# mqttSwitch2_0.net
KiCad netlist of a schematic drawn in EAGLE
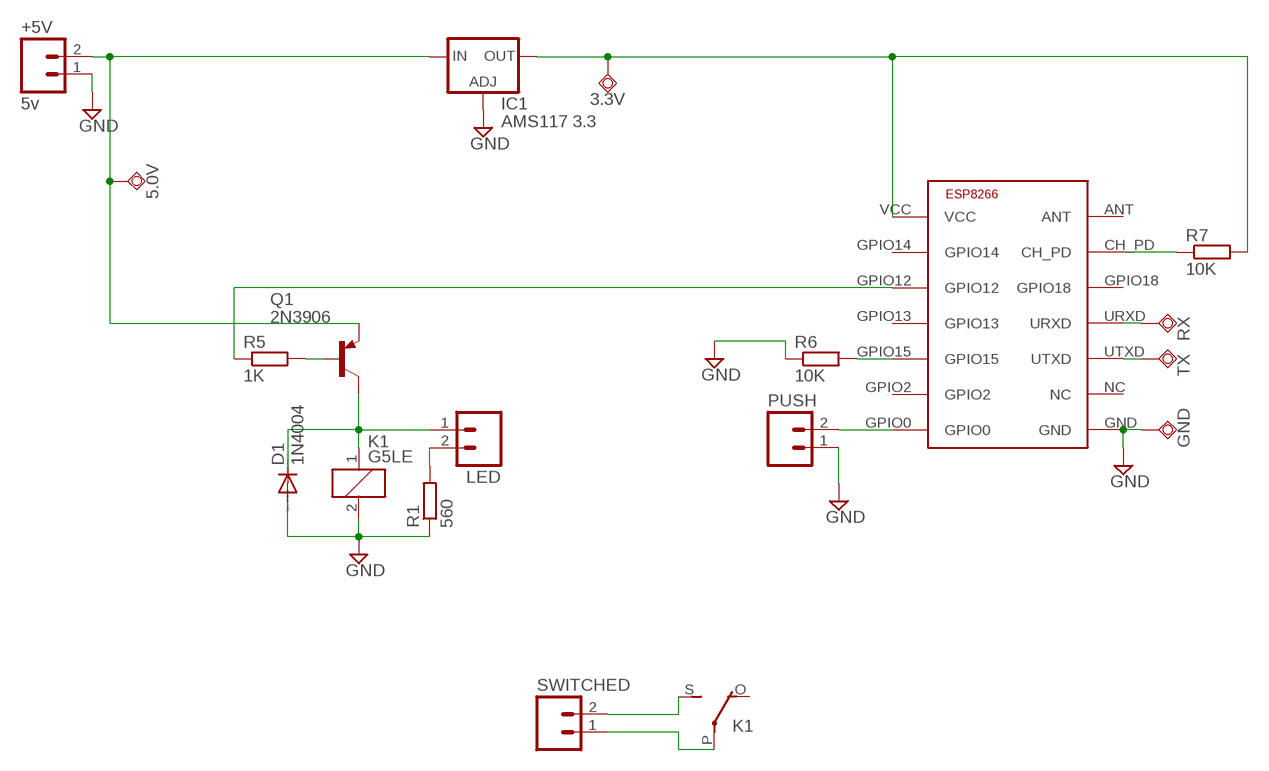
[diagram p0: schematic, sheet 1]

(export (version "E")
  (design (tool "Eeschema 10.0.6"))
  (components
    (comp (ref "+5V")
      (value "5v")
      (footprint "eagle-import:1X02")
      (libsource (lib "eagle-import") (part "M02PTH"))
    )
    (comp (ref "3.3V")
      (value "TPSQTP19R")
      (footprint "eagle-import:TP19R")
      (libsource (lib "eagle-import") (part "TPSQTP19R"))
    )
    (comp (ref "5.0V")
      (value "TPSQTP19R")
      (footprint "eagle-import:TP19R")
      (libsource (lib "eagle-import") (part "TPSQTP19R"))
    )
    (comp (ref "D1")
      (value "1N4004")
      (footprint "eagle-import:DO41-10")
      (libsource (lib "eagle-import") (part "1N4004"))
    )
    (comp (ref "GND")
      (value "TPSQTP19R")
      (footprint "eagle-import:TP19R")
      (libsource (lib "eagle-import") (part "TPSQTP19R"))
    )
    (comp (ref "IC1")
      (value "AMS117 3.3")
      (footprint "eagle-import:SOT223")
      (libsource (lib "eagle-import") (part "LD117A?S33TR"))
    )
    (comp (ref "K1")
      (value "G5LE")
      (footprint "eagle-import:G5LE")
      (libsource (lib "eagle-import") (part "G5LE"))
    )
    (comp (ref "LED")
      (value "M02PTH")
      (footprint "eagle-import:1X02")
      (libsource (lib "eagle-import") (part "M02PTH"))
    )
    (comp (ref "PUSH")
      (value "M02PTH")
      (footprint "eagle-import:1X02")
      (libsource (lib "eagle-import") (part "M02PTH"))
    )
    (comp (ref "Q1")
      (value "2N3906")
      (footprint "eagle-import:TO92")
      (libsource (lib "eagle-import") (part "2N3906"))
    )
    (comp (ref "R1")
      (value "560")
      (footprint "eagle-import:R0805")
      (libsource (lib "eagle-import") (part "R-EU_R0805"))
    )
    (comp (ref "R5")
      (value "1K")
      (footprint "eagle-import:R0805")
      (libsource (lib "eagle-import") (part "R-EU_R0805"))
    )
    (comp (ref "R6")
      (value "10K")
      (footprint "eagle-import:R0805")
      (libsource (lib "eagle-import") (part "R-EU_R0805"))
    )
    (comp (ref "R7")
      (value "10K")
      (footprint "eagle-import:R0805")
      (libsource (lib "eagle-import") (part "R-EU_R0805"))
    )
    (comp (ref "RX")
      (value "TPSQTP19R")
      (footprint "eagle-import:TP19R")
      (libsource (lib "eagle-import") (part "TPSQTP19R"))
    )
    (comp (ref "SWITCHED")
      (value "M02PTH4")
      (footprint "eagle-import:1X02_XTRA_BIG")
      (libsource (lib "eagle-import") (part "M02PTH4"))
    )
    (comp (ref "TX")
      (value "TPSQTP19R")
      (footprint "eagle-import:TP19R")
      (libsource (lib "eagle-import") (part "TPSQTP19R"))
    )
    (comp (ref "U$1")
      (value "ESP8266")
      (footprint "eagle-import:ESP-03")
      (libsource (lib "eagle-import") (part "ESP8266"))
    )
  )
  (nets
    (net (code "1") (name "GND") (class "Default")
      (node (ref "+5V") (pin "1") (pinfunction "1_1") (pintype "passive"))
      (node (ref "D1") (pin "A") (pinfunction "A_A") (pintype "passive"))
      (node (ref "GND") (pin "TP") (pinfunction "TP_TP") (pintype "input"))
      (node (ref "IC1") (pin "1") (pinfunction "ADJ_1") (pintype "input"))
      (node (ref "K1") (pin "2") (pinfunction "2_2") (pintype "passive"))
      (node (ref "PUSH") (pin "1") (pinfunction "1_1") (pintype "passive"))
      (node (ref "R1") (pin "1") (pinfunction "1_1") (pintype "passive"))
      (node (ref "R6") (pin "1") (pinfunction "1_1") (pintype "passive"))
      (node (ref "U$1") (pin "GND") (pinfunction "GND_GND") (pintype "bidirectional"))
    )
    (net (code "2") (name "Net-(IC1-IN)") (class "Default")
      (node (ref "+5V") (pin "2") (pinfunction "2_2") (pintype "passive"))
      (node (ref "5.0V") (pin "TP") (pinfunction "TP_TP") (pintype "input"))
      (node (ref "IC1") (pin "3") (pinfunction "IN_3") (pintype "input"))
      (node (ref "Q1") (pin "3") (pinfunction "E_3") (pintype "passive"))
    )
    (net (code "3") (name "Net-(IC1-OUT)") (class "Default")
      (node (ref "3.3V") (pin "TP") (pinfunction "TP_TP") (pintype "input"))
      (node (ref "IC1") (pin "4") (pinfunction "OUT_4") (pintype "passive"))
      (node (ref "R7") (pin "2") (pinfunction "2_2") (pintype "passive"))
      (node (ref "U$1") (pin "VCC") (pinfunction "VCC_VCC") (pintype "bidirectional"))
    )
    (net (code "4") (name "Net-(K1-PadP)") (class "Default")
      (node (ref "K1") (pin "P") (pinfunction "P_P") (pintype "passive"))
      (node (ref "SWITCHED") (pin "1") (pinfunction "1_1") (pintype "passive"))
    )
    (net (code "5") (name "Net-(K1-PadS)") (class "Default")
      (node (ref "K1") (pin "S") (pinfunction "S_S") (pintype "passive"))
      (node (ref "SWITCHED") (pin "2") (pinfunction "2_2") (pintype "passive"))
    )
    (net (code "6") (name "Net-(LED-Pad2)") (class "Default")
      (node (ref "LED") (pin "2") (pinfunction "2_2") (pintype "passive"))
      (node (ref "R1") (pin "2") (pinfunction "2_2") (pintype "passive"))
    )
    (net (code "7") (name "Net-(PUSH-Pad2)") (class "Default")
      (node (ref "PUSH") (pin "2") (pinfunction "2_2") (pintype "passive"))
      (node (ref "U$1") (pin "GPIO0") (pinfunction "GPIO0_GPIO0") (pintype "bidirectional"))
    )
    (net (code "8") (name "Net-(Q1-B)") (class "Default")
      (node (ref "Q1") (pin "2") (pinfunction "B_2") (pintype "passive"))
      (node (ref "R5") (pin "2") (pinfunction "2_2") (pintype "passive"))
    )
    (net (code "9") (name "Net-(Q1-C)") (class "Default")
      (node (ref "D1") (pin "C") (pinfunction "C_C") (pintype "passive"))
      (node (ref "K1") (pin "1") (pinfunction "1_1") (pintype "passive"))
      (node (ref "LED") (pin "1") (pinfunction "1_1") (pintype "passive"))
      (node (ref "Q1") (pin "1") (pinfunction "C_1") (pintype "passive"))
    )
    (net (code "10") (name "Net-(R5-Pad1)") (class "Default")
      (node (ref "R5") (pin "1") (pinfunction "1_1") (pintype "passive"))
      (node (ref "U$1") (pin "GPIO12") (pinfunction "GPIO12_GPIO12") (pintype "bidirectional"))
    )
    (net (code "11") (name "Net-(R6-Pad2)") (class "Default")
      (node (ref "R6") (pin "2") (pinfunction "2_2") (pintype "passive"))
      (node (ref "U$1") (pin "GPIO15") (pinfunction "GPIO15_GPIO15") (pintype "bidirectional"))
    )
    (net (code "12") (name "Net-(R7-Pad1)") (class "Default")
      (node (ref "R7") (pin "1") (pinfunction "1_1") (pintype "passive"))
      (node (ref "U$1") (pin "CH_PD") (pinfunction "CH_PD_CH_PD") (pintype "bidirectional"))
    )
    (net (code "13") (name "Net-(RX-PadTP)") (class "Default")
      (node (ref "RX") (pin "TP") (pinfunction "TP_TP") (pintype "input"))
      (node (ref "U$1") (pin "URXD") (pinfunction "URXD_URXD") (pintype "bidirectional"))
    )
    (net (code "14") (name "Net-(TX-PadTP)") (class "Default")
      (node (ref "TX") (pin "TP") (pinfunction "TP_TP") (pintype "input"))
      (node (ref "U$1") (pin "UTXD") (pinfunction "UTXD_UTXD") (pintype "bidirectional"))
    )
    (net (code "15") (name "unconnected-(K1-PadO)") (class "Default")
      (node (ref "K1") (pin "O") (pinfunction "O_O") (pintype "passive"))
    )
    (net (code "16") (name "unconnected-(U$1-PadANT)") (class "Default")
      (node (ref "U$1") (pin "ANT") (pinfunction "ANT_ANT") (pintype "bidirectional"))
    )
    (net (code "17") (name "unconnected-(U$1-PadGPIO2)") (class "Default")
      (node (ref "U$1") (pin "GPIO2") (pinfunction "GPIO2_GPIO2") (pintype "bidirectional"))
    )
    (net (code "18") (name "unconnected-(U$1-PadGPIO13)") (class "Default")
      (node (ref "U$1") (pin "GPIO13") (pinfunction "GPIO13_GPIO13") (pintype "bidirectional"))
    )
    (net (code "19") (name "unconnected-(U$1-PadGPIO14)") (class "Default")
      (node (ref "U$1") (pin "GPIO14") (pinfunction "GPIO14_GPIO14") (pintype "bidirectional"))
    )
    (net (code "20") (name "unconnected-(U$1-PadGPIO18)") (class "Default")
      (node (ref "U$1") (pin "GPIO18") (pinfunction "GPIO18_GPIO18") (pintype "bidirectional"))
    )
    (net (code "21") (name "unconnected-(U$1-PadNC)") (class "Default")
      (node (ref "U$1") (pin "NC") (pinfunction "NC_NC") (pintype "bidirectional"))
    )
  )
)
